# mp28164-buck-boost-flashlight-driver-tes.net
KiCad netlist of a schematic drawn in EAGLE
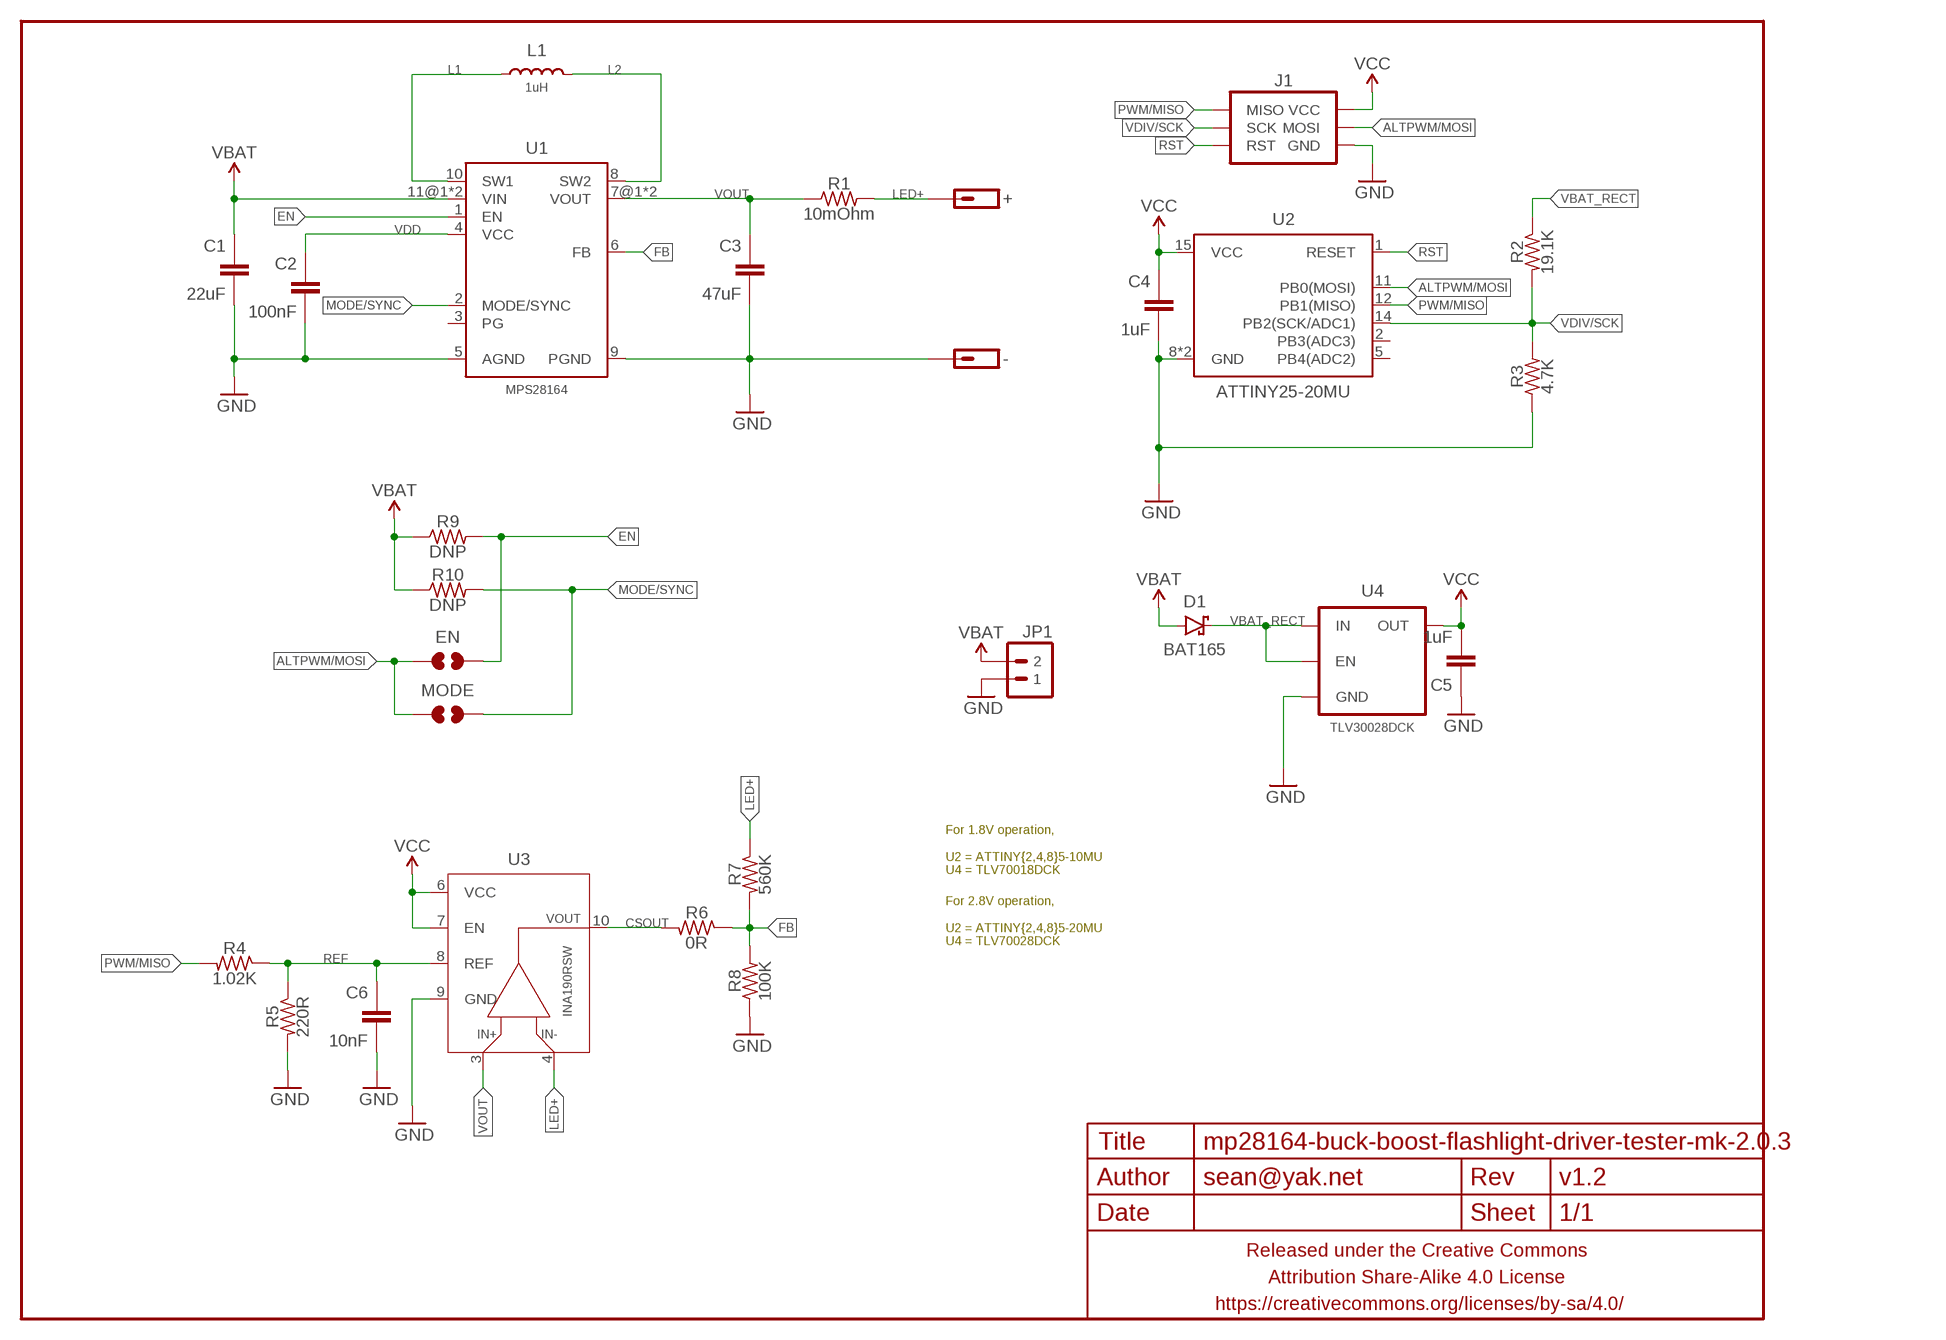
[diagram p0: schematic, sheet 1]

(export (version "E")
  (design (tool "Eeschema 10.0.6"))
  (components
    (comp (ref "+")
      (value "M01PTH-1.2MM-NS")
      (footprint "eagle-import:1X01-1.2MM-NS")
      (libsource (lib "eagle-import") (part "M01PTH-1.2MM-NS"))
    )
    (comp (ref "-")
      (value "M01PTH-1.2MM-NS")
      (footprint "eagle-import:1X01-1.2MM-NS")
      (libsource (lib "eagle-import") (part "M01PTH-1.2MM-NS"))
    )
    (comp (ref "C1")
      (value "22uF")
      (footprint "eagle-import:C1206")
      (libsource (lib "eagle-import") (part "CAPACITOR-CERAMICC1206"))
    )
    (comp (ref "C2")
      (value "100nF")
      (footprint "eagle-import:C0402")
      (libsource (lib "eagle-import") (part "CAPACITOR-CERAMICC0402"))
    )
    (comp (ref "C3")
      (value "47uF")
      (footprint "eagle-import:C1206")
      (libsource (lib "eagle-import") (part "CAPACITOR-CERAMICC1206"))
    )
    (comp (ref "C4")
      (value "1uF")
      (footprint "eagle-import:C0402")
      (libsource (lib "eagle-import") (part "CAPACITOR-CERAMICC0402"))
    )
    (comp (ref "C5")
      (value "1uF")
      (footprint "eagle-import:C0402")
      (libsource (lib "eagle-import") (part "CAPACITOR-CERAMICC0402"))
    )
    (comp (ref "C6")
      (value "10nF")
      (footprint "eagle-import:C0402")
      (libsource (lib "eagle-import") (part "CAPACITOR-CERAMICC0402"))
    )
    (comp (ref "D1")
      (value "BAT165")
      (footprint "eagle-import:SOD323-SCHOTTKY")
      (libsource (lib "eagle-import") (part "DIODE-SCHOTTKYSOD323"))
    )
    (comp (ref "EN")
      (value "JUMPER-PAD-2-NOYES_SILK")
      (footprint "eagle-import:PAD-JUMPER-2-NO_YES_SILK")
      (libsource (lib "eagle-import") (part "JUMPER-PAD-2-NOYES_SILK"))
    )
    (comp (ref "FRAME1")
      (value "FRAME-LETTERNO_PACKAGE")
      (footprint "eagle-import:DUMMY")
      (fields
        (field (name "DESIGNER") "sean@yak.net")
        (field (name "VERSION") "v1.2")
        (field (name "DESIGNER_1") "sean@yak.net")
        (field (name "VERSION_1") "v1.2")
      )
      (libsource (lib "eagle-import") (part "FRAME-LETTERNO_PACKAGE"))
    )
    (comp (ref "J1")
      (value "AVR_SPI_PRG_6PTH")
      (footprint "eagle-import:2X3")
      (libsource (lib "eagle-import") (part "AVR_SPI_PRG_6PTH"))
    )
    (comp (ref "JP1")
      (value "M02PTH-CENTERED")
      (footprint "eagle-import:1X02-CENTER")
      (libsource (lib "eagle-import") (part "M02PTH-CENTERED"))
    )
    (comp (ref "L1")
      (value "1uH")
      (footprint "eagle-import:XAL60XX")
      (libsource (lib "eagle-import") (part "INDUCTORXAL60XX"))
    )
    (comp (ref "MODE")
      (value "JUMPER-PAD-2-NOYES_SILK")
      (footprint "eagle-import:PAD-JUMPER-2-NO_YES_SILK")
      (libsource (lib "eagle-import") (part "JUMPER-PAD-2-NOYES_SILK"))
    )
    (comp (ref "R1")
      (value "10mOhm")
      (footprint "eagle-import:R1206")
      (libsource (lib "eagle-import") (part "RESISTORR1206"))
    )
    (comp (ref "R2")
      (value "19.1K")
      (footprint "eagle-import:R0402")
      (libsource (lib "eagle-import") (part "RESISTORR0402"))
    )
    (comp (ref "R3")
      (value "4.7K")
      (footprint "eagle-import:R0402")
      (libsource (lib "eagle-import") (part "RESISTORR0402"))
    )
    (comp (ref "R4")
      (value "1.02K")
      (footprint "eagle-import:R0402")
      (libsource (lib "eagle-import") (part "RESISTORR0402"))
    )
    (comp (ref "R5")
      (value "220R")
      (footprint "eagle-import:R0402")
      (libsource (lib "eagle-import") (part "RESISTORR0402"))
    )
    (comp (ref "R6")
      (value "0R")
      (footprint "eagle-import:R0402")
      (libsource (lib "eagle-import") (part "RESISTORR0402"))
    )
    (comp (ref "R7")
      (value "560K")
      (footprint "eagle-import:R0402")
      (libsource (lib "eagle-import") (part "RESISTORR0402"))
    )
    (comp (ref "R8")
      (value "100K")
      (footprint "eagle-import:R0402")
      (libsource (lib "eagle-import") (part "RESISTORR0402"))
    )
    (comp (ref "R9")
      (value "DNP")
      (footprint "eagle-import:R0402")
      (libsource (lib "eagle-import") (part "RESISTORR0402"))
    )
    (comp (ref "R10")
      (value "DNP")
      (footprint "eagle-import:R0402")
      (libsource (lib "eagle-import") (part "RESISTORR0402"))
    )
    (comp (ref "U1")
      (value "MPS28164")
      (footprint "eagle-import:MPS28164")
      (libsource (lib "eagle-import") (part "MPS28164"))
    )
    (comp (ref "U2")
      (value "ATTINY25-20MU")
      (footprint "eagle-import:QFN20")
      (libsource (lib "eagle-import") (part "ATTINY45TINY85-20-QFN"))
    )
    (comp (ref "U3")
      (value "INA190RSW")
      (footprint "eagle-import:UQFN-10")
      (libsource (lib "eagle-import") (part "INA190RSW"))
    )
    (comp (ref "U4")
      (value "TLV30028DCK")
      (footprint "eagle-import:SC70")
      (libsource (lib "eagle-import") (part "V_REG_ENTLV700XXDCR"))
    )
  )
  (nets
    (net (code "1") (name "/CSOUT") (class "Default")
      (node (ref "R6") (pin "2") (pinfunction "2_2") (pintype "passive"))
      (node (ref "U3") (pin "10") (pinfunction "OUT_10") (pintype "bidirectional"))
    )
    (net (code "2") (name "/L1") (class "Default")
      (node (ref "L1") (pin "P$1") (pinfunction "1_P$1") (pintype "passive"))
      (node (ref "U1") (pin "10") (pinfunction "SW1_10") (pintype "bidirectional"))
    )
    (net (code "3") (name "/L2") (class "Default")
      (node (ref "L1") (pin "P$2") (pinfunction "2_P$2") (pintype "passive"))
      (node (ref "U1") (pin "8") (pinfunction "SW2_8") (pintype "bidirectional"))
    )
    (net (code "4") (name "/REF") (class "Default")
      (node (ref "C6") (pin "1") (pinfunction "1_1") (pintype "passive"))
      (node (ref "R4") (pin "1") (pinfunction "1_1") (pintype "passive"))
      (node (ref "R5") (pin "1") (pinfunction "1_1") (pintype "passive"))
      (node (ref "U3") (pin "8") (pinfunction "REF_8") (pintype "bidirectional"))
    )
    (net (code "5") (name "/VDD") (class "Default")
      (node (ref "C2") (pin "1") (pinfunction "1_1") (pintype "passive"))
      (node (ref "U1") (pin "4") (pinfunction "VCC_4") (pintype "bidirectional"))
    )
    (net (code "6") (name "ALTPWM{slash}MOSI") (class "Default")
      (node (ref "EN") (pin "1") (pinfunction "1_1") (pintype "passive"))
      (node (ref "J1") (pin "4") (pinfunction "MOSI_4") (pintype "passive"))
      (node (ref "MODE") (pin "1") (pinfunction "1_1") (pintype "passive"))
      (node (ref "U2") (pin "11") (pinfunction "PB0(MOSI)_11") (pintype "bidirectional"))
    )
    (net (code "7") (name "EN") (class "Default")
      (node (ref "EN") (pin "2") (pinfunction "2_2") (pintype "passive"))
      (node (ref "R9") (pin "2") (pinfunction "2_2") (pintype "passive"))
      (node (ref "U1") (pin "1") (pinfunction "EN_1") (pintype "bidirectional"))
    )
    (net (code "8") (name "FB") (class "Default")
      (node (ref "R6") (pin "1") (pinfunction "1_1") (pintype "passive"))
      (node (ref "R7") (pin "2") (pinfunction "2_2") (pintype "passive"))
      (node (ref "R8") (pin "2") (pinfunction "2_2") (pintype "passive"))
      (node (ref "U1") (pin "6") (pinfunction "FB_6") (pintype "bidirectional"))
    )
    (net (code "9") (name "GND") (class "Default")
      (node (ref "-") (pin "P$1") (pinfunction "1_P$1") (pintype "passive"))
      (node (ref "C1") (pin "2") (pinfunction "2_2") (pintype "passive"))
      (node (ref "C2") (pin "2") (pinfunction "2_2") (pintype "passive"))
      (node (ref "C3") (pin "2") (pinfunction "2_2") (pintype "passive"))
      (node (ref "C4") (pin "2") (pinfunction "2_2") (pintype "passive"))
      (node (ref "C5") (pin "1") (pinfunction "1_1") (pintype "passive"))
      (node (ref "C6") (pin "2") (pinfunction "2_2") (pintype "passive"))
      (node (ref "J1") (pin "6") (pinfunction "GND_6") (pintype "passive"))
      (node (ref "JP1") (pin "1") (pinfunction "1_1") (pintype "passive"))
      (node (ref "R3") (pin "1") (pinfunction "1_1") (pintype "passive"))
      (node (ref "R5") (pin "2") (pinfunction "2_2") (pintype "passive"))
      (node (ref "R8") (pin "1") (pinfunction "1_1") (pintype "passive"))
      (node (ref "U1") (pin "5") (pinfunction "AGND_5") (pintype "bidirectional"))
      (node (ref "U1") (pin "9") (pinfunction "PGND_9") (pintype "bidirectional"))
      (node (ref "U2") (pin "8") (pinfunction "GND_8") (pintype "bidirectional"))
      (node (ref "U2") (pin "PAD") (pinfunction "GND_PAD") (pintype "bidirectional"))
      (node (ref "U3") (pin "9") (pinfunction "GND_9") (pintype "bidirectional"))
      (node (ref "U4") (pin "2") (pinfunction "GND_2") (pintype "input"))
    )
    (net (code "10") (name "LED+") (class "Default")
      (node (ref "+") (pin "P$1") (pinfunction "1_P$1") (pintype "passive"))
      (node (ref "R1") (pin "2") (pinfunction "2_2") (pintype "passive"))
      (node (ref "R7") (pin "1") (pinfunction "1_1") (pintype "passive"))
      (node (ref "U3") (pin "4") (pinfunction "VIN-_4") (pintype "bidirectional"))
    )
    (net (code "11") (name "MODE{slash}SYNC") (class "Default")
      (node (ref "MODE") (pin "2") (pinfunction "2_2") (pintype "passive"))
      (node (ref "R10") (pin "2") (pinfunction "2_2") (pintype "passive"))
      (node (ref "U1") (pin "2") (pinfunction "MODE/SYNC_2") (pintype "bidirectional"))
    )
    (net (code "12") (name "PWM{slash}MISO") (class "Default")
      (node (ref "J1") (pin "1") (pinfunction "MISO_1") (pintype "passive"))
      (node (ref "R4") (pin "2") (pinfunction "2_2") (pintype "passive"))
      (node (ref "U2") (pin "12") (pinfunction "PB1(MISO)_12") (pintype "bidirectional"))
    )
    (net (code "13") (name "RST") (class "Default")
      (node (ref "J1") (pin "5") (pinfunction "RST_5") (pintype "passive"))
      (node (ref "U2") (pin "1") (pinfunction "RESET_1") (pintype "bidirectional"))
    )
    (net (code "14") (name "VBAT") (class "Default")
      (node (ref "C1") (pin "1") (pinfunction "1_1") (pintype "passive"))
      (node (ref "D1") (pin "A") (pinfunction "A_A") (pintype "passive"))
      (node (ref "JP1") (pin "2") (pinfunction "2_2") (pintype "passive"))
      (node (ref "R10") (pin "1") (pinfunction "1_1") (pintype "passive"))
      (node (ref "R9") (pin "1") (pinfunction "1_1") (pintype "passive"))
      (node (ref "U1") (pin "11@1") (pinfunction "VIN_11@1") (pintype "bidirectional"))
      (node (ref "U1") (pin "11@2") (pinfunction "VIN_11@2") (pintype "bidirectional"))
    )
    (net (code "15") (name "VBAT_RECT") (class "Default")
      (node (ref "D1") (pin "C") (pinfunction "C_C") (pintype "passive"))
      (node (ref "R2") (pin "1") (pinfunction "1_1") (pintype "passive"))
      (node (ref "U4") (pin "1") (pinfunction "IN_1") (pintype "input"))
      (node (ref "U4") (pin "3") (pinfunction "EN_3") (pintype "input"))
    )
    (net (code "16") (name "VCC") (class "Default")
      (node (ref "C4") (pin "1") (pinfunction "1_1") (pintype "passive"))
      (node (ref "C5") (pin "2") (pinfunction "2_2") (pintype "passive"))
      (node (ref "J1") (pin "2") (pinfunction "VCC_2") (pintype "passive"))
      (node (ref "U2") (pin "15") (pinfunction "VCC_15") (pintype "bidirectional"))
      (node (ref "U3") (pin "6") (pinfunction "VCC_6") (pintype "bidirectional"))
      (node (ref "U3") (pin "7") (pinfunction "EN_7") (pintype "bidirectional"))
      (node (ref "U4") (pin "5") (pinfunction "OUT_5") (pintype "passive"))
    )
    (net (code "17") (name "VDIV{slash}SCK") (class "Default")
      (node (ref "J1") (pin "3") (pinfunction "SCK_3") (pintype "passive"))
      (node (ref "R2") (pin "2") (pinfunction "2_2") (pintype "passive"))
      (node (ref "R3") (pin "2") (pinfunction "2_2") (pintype "passive"))
      (node (ref "U2") (pin "14") (pinfunction "PB2(SCK/ADC1)_14") (pintype "bidirectional"))
    )
    (net (code "18") (name "VOUT") (class "Default")
      (node (ref "C3") (pin "1") (pinfunction "1_1") (pintype "passive"))
      (node (ref "R1") (pin "1") (pinfunction "1_1") (pintype "passive"))
      (node (ref "U1") (pin "7@1") (pinfunction "VOUT_7@1") (pintype "bidirectional"))
      (node (ref "U1") (pin "7@2") (pinfunction "VOUT_7@2") (pintype "bidirectional"))
      (node (ref "U3") (pin "3") (pinfunction "VIN+_3") (pintype "bidirectional"))
    )
    (net (code "19") (name "unconnected-(U1-PG-Pad3)") (class "Default")
      (node (ref "U1") (pin "3") (pinfunction "PG_3") (pintype "bidirectional"))
    )
    (net (code "20") (name "unconnected-(U2-PB3(ADC3)-Pad2)") (class "Default")
      (node (ref "U2") (pin "2") (pinfunction "PB3(ADC3)_2") (pintype "bidirectional"))
    )
    (net (code "21") (name "unconnected-(U2-PB4(ADC2)-Pad5)") (class "Default")
      (node (ref "U2") (pin "5") (pinfunction "PB4(ADC2)_5") (pintype "bidirectional"))
    )
  )
)
